# INA219.net
KiCad netlist of a schematic drawn in EAGLE
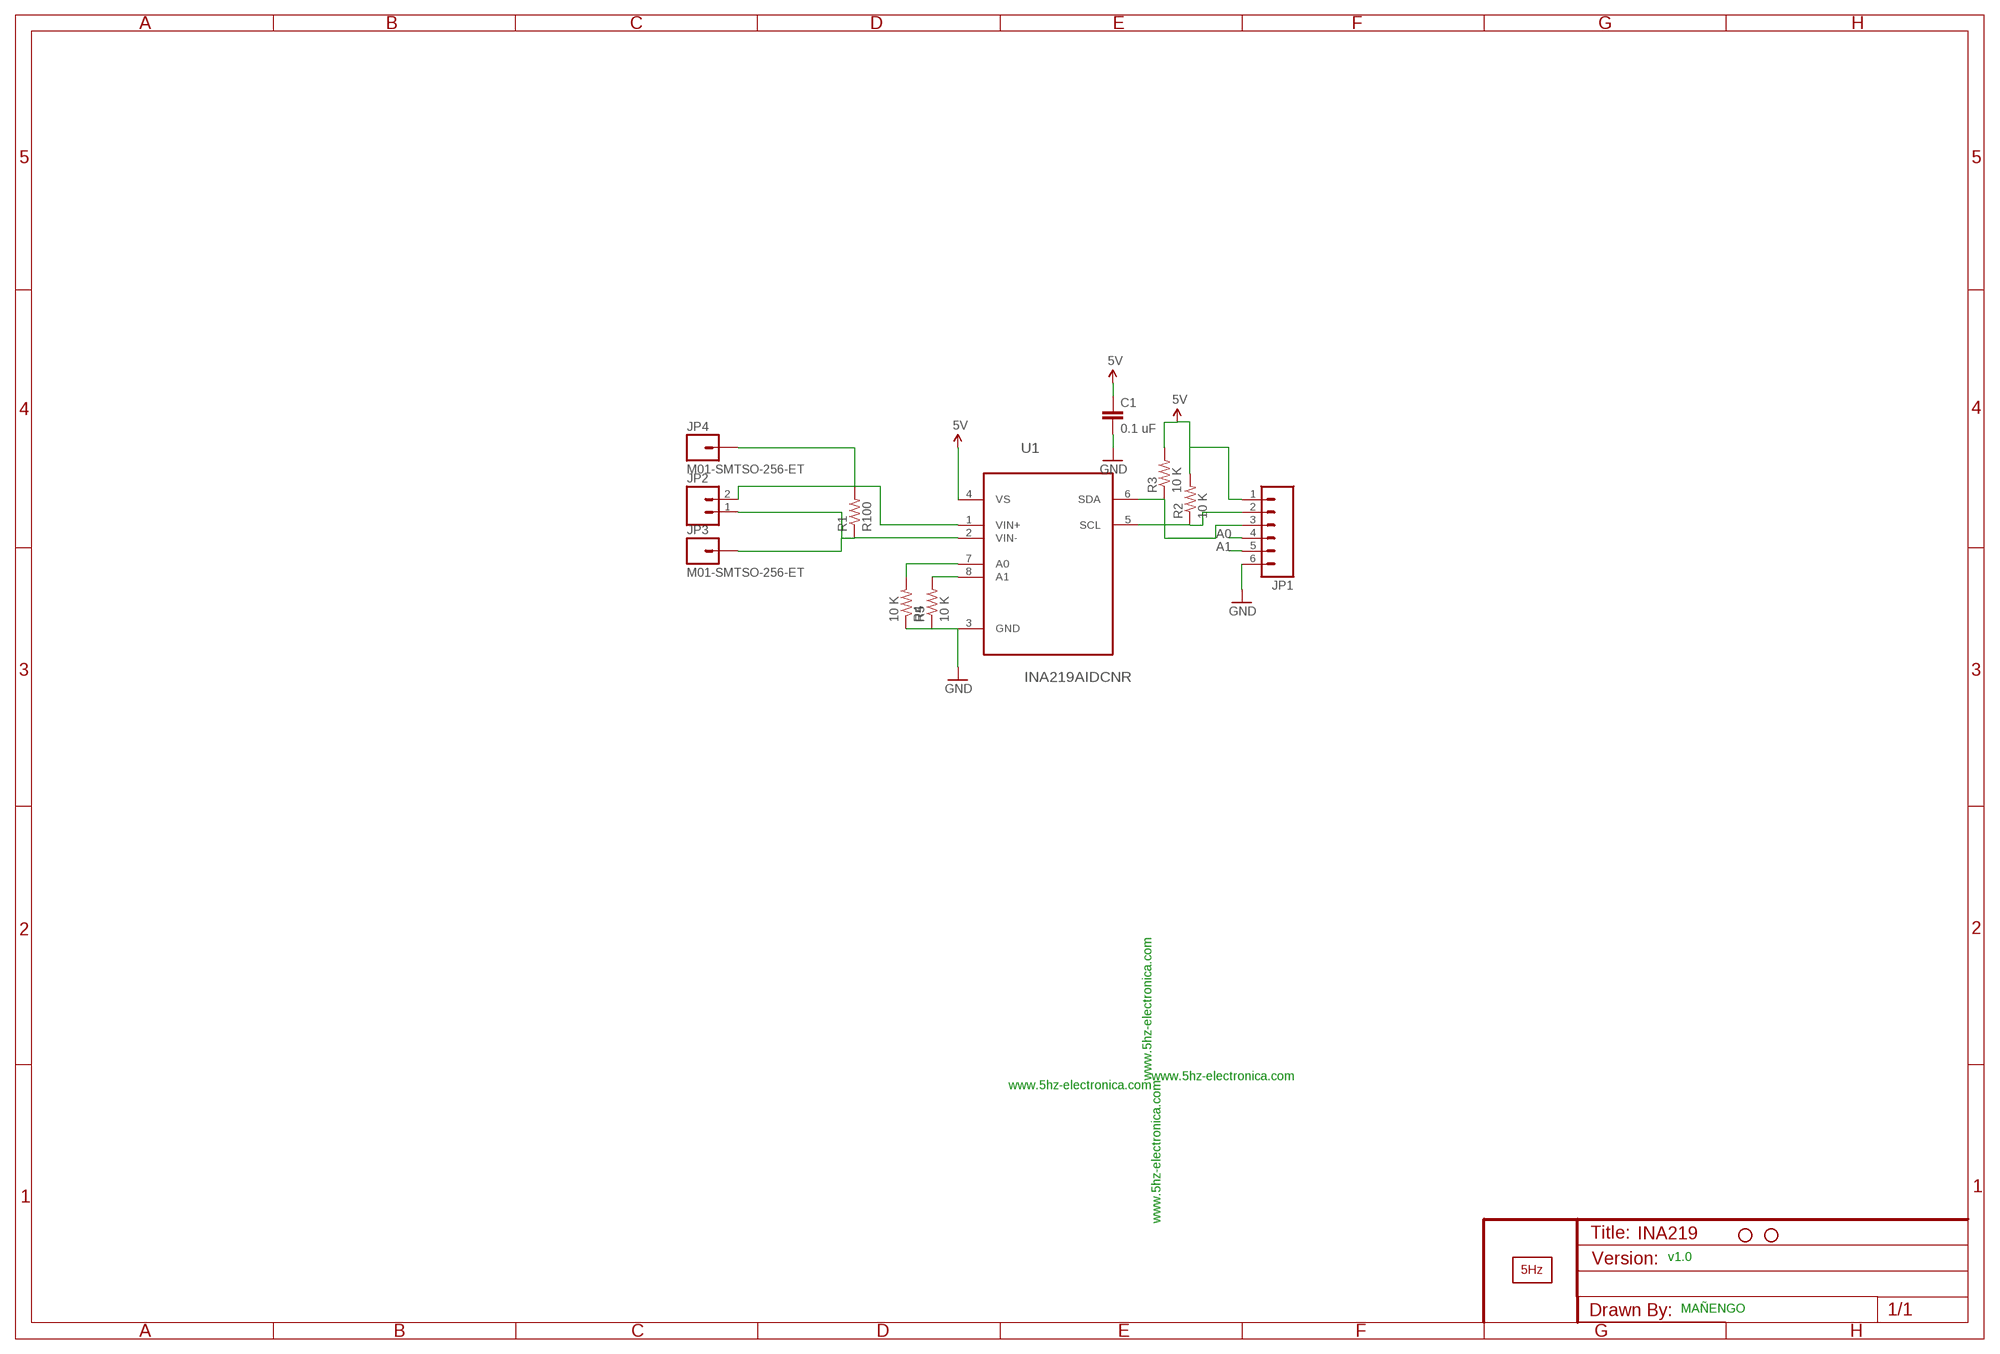
[diagram p0: schematic, sheet 1]

(export (version "E")
  (design (tool "Eeschema 10.0.6"))
  (components
    (comp (ref "C1")
      (value "0.1 uF")
      (footprint "eagle-import:0603-CAP")
      (libsource (lib "eagle-import") (part "CAP0603-CAP"))
    )
    (comp (ref "JP1")
      (value "M06SIP")
      (footprint "eagle-import:1X06")
      (libsource (lib "eagle-import") (part "M06SIP"))
    )
    (comp (ref "JP2")
      (value "M023.5MM-NO_SILK")
      (footprint "eagle-import:SCREWTERMINAL-3.5MM-2-NS")
      (libsource (lib "eagle-import") (part "M023.5MM-NO_SILK"))
    )
    (comp (ref "JP3")
      (value "M01-SMTSO-256-ET")
      (footprint "eagle-import:SMTSO-256-ET")
      (libsource (lib "eagle-import") (part "M01-SMTSO-256-ET"))
    )
    (comp (ref "JP4")
      (value "M01-SMTSO-256-ET")
      (footprint "eagle-import:SMTSO-256-ET")
      (libsource (lib "eagle-import") (part "M01-SMTSO-256-ET"))
    )
    (comp (ref "JP5")
      (value "STAND-OFF")
      (footprint "eagle-import:STAND-OFF")
      (libsource (lib "eagle-import") (part "STAND-OFF"))
    )
    (comp (ref "JP6")
      (value "STAND-OFF")
      (footprint "eagle-import:STAND-OFF")
      (libsource (lib "eagle-import") (part "STAND-OFF"))
    )
    (comp (ref "R1")
      (value "R100")
      (footprint "eagle-import:R2512")
      (libsource (lib "eagle-import") (part "RESISTOR2512"))
    )
    (comp (ref "R2")
      (value "10 K")
      (footprint "eagle-import:0603-RES")
      (libsource (lib "eagle-import") (part "RESISTOR0603-RES"))
    )
    (comp (ref "R3")
      (value "10 K")
      (footprint "eagle-import:0603-RES")
      (libsource (lib "eagle-import") (part "RESISTOR0603-RES"))
    )
    (comp (ref "R4")
      (value "10 K")
      (footprint "eagle-import:0603-RES")
      (libsource (lib "eagle-import") (part "RESISTOR0603-RES"))
    )
    (comp (ref "R5")
      (value "10 K")
      (footprint "eagle-import:0603-RES")
      (libsource (lib "eagle-import") (part "RESISTOR0603-RES"))
    )
    (comp (ref "U$5")
      (value "LOGO2_SILK5MM")
      (footprint "eagle-import:LOGO2_5MM")
      (libsource (lib "eagle-import") (part "LOGO2_SILK5MM"))
    )
    (comp (ref "U1")
      (value "INA219AIDCNR")
      (footprint "eagle-import:SOT65P280X145-8N")
      (libsource (lib "eagle-import") (part "INA219AIDCNR"))
    )
  )
  (nets
    (net (code "1") (name "/A0") (class "Default")
      (node (ref "JP1") (pin "4") (pinfunction "4_4") (pintype "passive"))
      (node (ref "R4") (pin "2") (pinfunction "2_2") (pintype "passive"))
      (node (ref "U1") (pin "7") (pinfunction "A0_7") (pintype "input"))
    )
    (net (code "2") (name "/A1") (class "Default")
      (node (ref "JP1") (pin "5") (pinfunction "5_5") (pintype "passive"))
      (node (ref "R5") (pin "2") (pinfunction "2_2") (pintype "passive"))
      (node (ref "U1") (pin "8") (pinfunction "A1_8") (pintype "input"))
    )
    (net (code "3") (name "5V") (class "Default")
      (node (ref "C1") (pin "1") (pinfunction "1_1") (pintype "passive"))
      (node (ref "JP1") (pin "1") (pinfunction "1_1") (pintype "passive"))
      (node (ref "R2") (pin "2") (pinfunction "2_2") (pintype "passive"))
      (node (ref "R3") (pin "2") (pinfunction "2_2") (pintype "passive"))
      (node (ref "U1") (pin "4") (pinfunction "VS_4") (pintype "power_in"))
    )
    (net (code "4") (name "GND") (class "Default")
      (node (ref "C1") (pin "2") (pinfunction "2_2") (pintype "passive"))
      (node (ref "JP1") (pin "6") (pinfunction "6_6") (pintype "passive"))
      (node (ref "R4") (pin "1") (pinfunction "1_1") (pintype "passive"))
      (node (ref "R5") (pin "1") (pinfunction "1_1") (pintype "passive"))
      (node (ref "U1") (pin "3") (pinfunction "GND_3") (pintype "passive"))
    )
    (net (code "5") (name "Net-(JP3-1)") (class "Default")
      (node (ref "JP2") (pin "1") (pinfunction "1_1") (pintype "passive"))
      (node (ref "JP3") (pin "P$1") (pinfunction "1_P$1") (pintype "passive"))
      (node (ref "R1") (pin "1") (pinfunction "1_1") (pintype "passive"))
      (node (ref "U1") (pin "2") (pinfunction "VIN-_2") (pintype "input"))
    )
    (net (code "6") (name "Net-(JP4-1)") (class "Default")
      (node (ref "JP2") (pin "2") (pinfunction "2_2") (pintype "passive"))
      (node (ref "JP4") (pin "P$1") (pinfunction "1_P$1") (pintype "passive"))
      (node (ref "R1") (pin "2") (pinfunction "2_2") (pintype "passive"))
      (node (ref "U1") (pin "1") (pinfunction "VIN+_1") (pintype "input"))
    )
    (net (code "7") (name "Net-(U1-SCL)") (class "Default")
      (node (ref "JP1") (pin "2") (pinfunction "2_2") (pintype "passive"))
      (node (ref "R2") (pin "1") (pinfunction "1_1") (pintype "passive"))
      (node (ref "U1") (pin "5") (pinfunction "SCL_5") (pintype "input"))
    )
    (net (code "8") (name "Net-(U1-SDA)") (class "Default")
      (node (ref "JP1") (pin "3") (pinfunction "3_3") (pintype "passive"))
      (node (ref "R3") (pin "1") (pinfunction "1_1") (pintype "passive"))
      (node (ref "U1") (pin "6") (pinfunction "SDA_6") (pintype "bidirectional"))
    )
  )
)
